# mainboard_V2_1.net
KiCad netlist of a schematic drawn in EasyEDA Pro
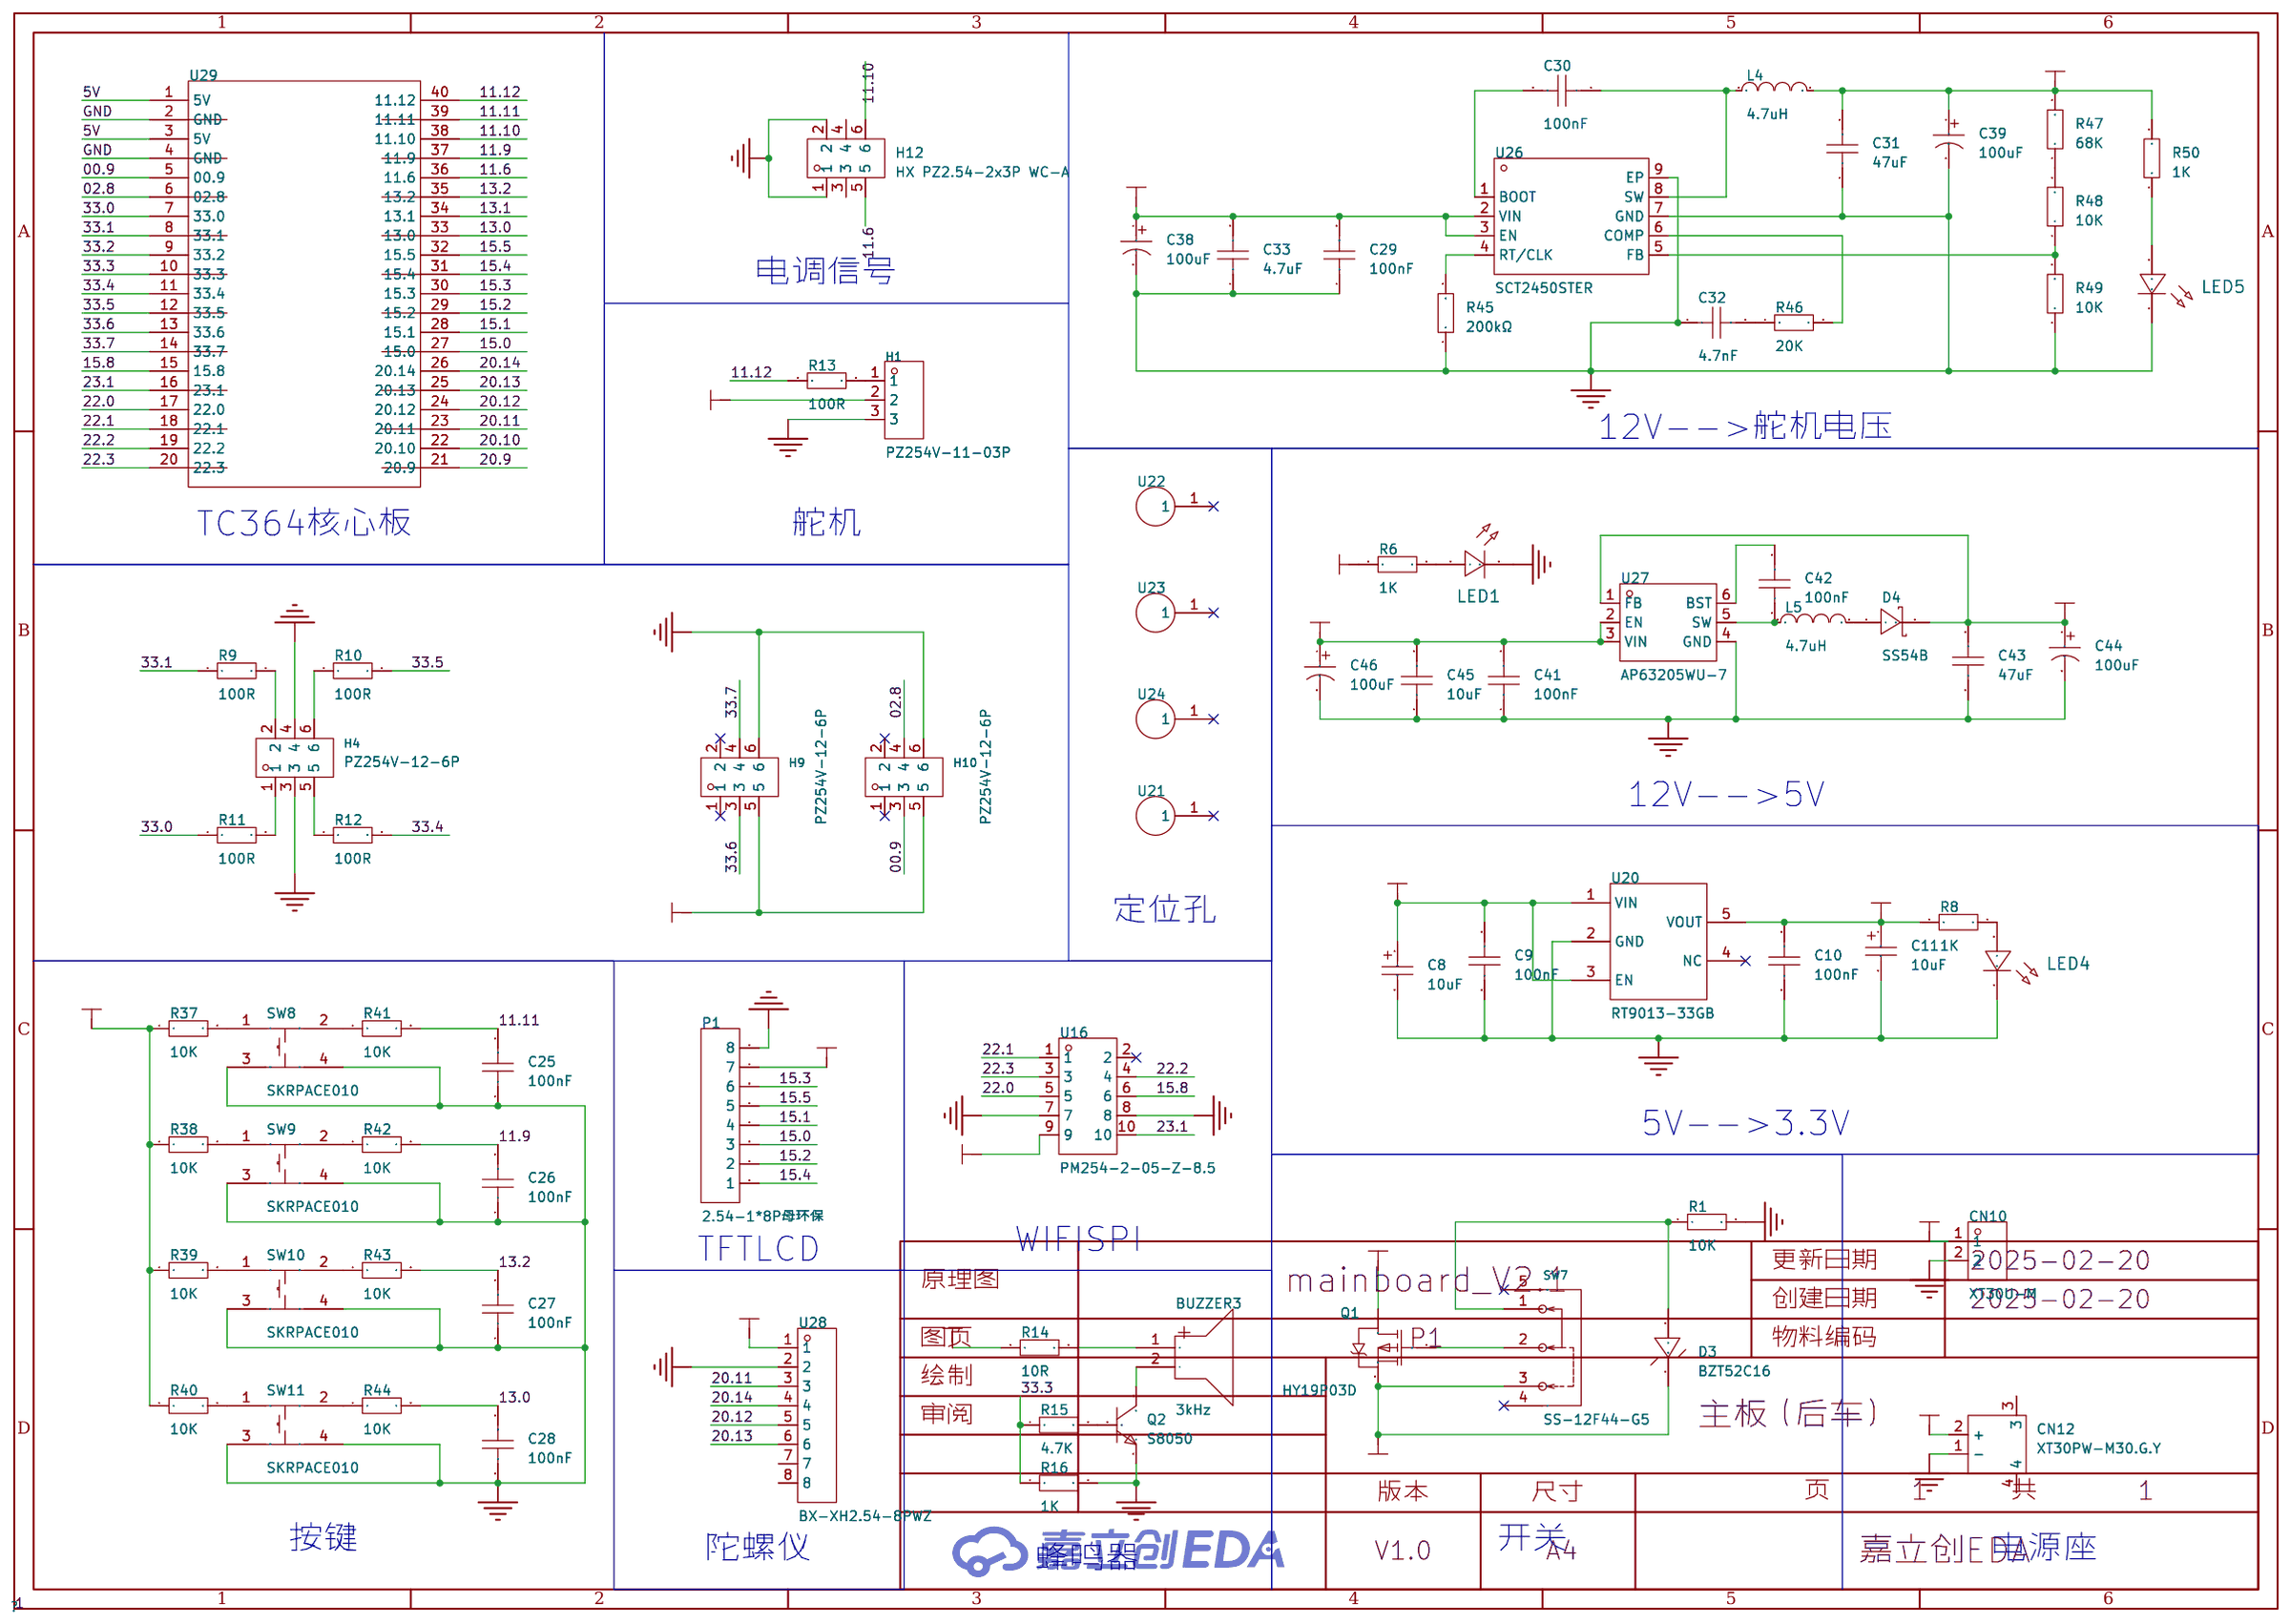
[diagram p0: schematic sheet]

(export (version "E")
  (design (tool "Eeschema 10.0.6"))
  (components
    (comp (ref "BUZZER3")
      (value "3kHz")
      (footprint "easyedapro:BUZ-TH_BD9.0-P5.00-D0.6-FD")
      (description "驱动方式:有源(内含驱动线路);构造类型:电磁式;频率:3kHz;声压(SPL):85dB@10cm;")
      (fields (field (name "Manufacturer Part") "HNB09A03") (field (name "Manufacturer") "华能"))
      (libsource (lib "easyedapro") (part "HNB09A03"))
    )
    (comp (ref "C8")
      (value "10uF")
      (footprint "easyedapro:CAP-SMD_L3.2-W1.6-RD-C7171")
      (description "容值:10uF;精度:±10%;额定电压:16V;等效串联电阻:3Ω@100kHz;")
      (fields (field (name "Manufacturer Part") "TAJA106K016RNJ") (field (name "Manufacturer") "Kyocera AVX"))
      (libsource (lib "easyedapro") (part "TAJA106K016RNJ"))
    )
    (comp (ref "C9")
      (value "100nF")
      (footprint "easyedapro:C0603")
      (description "容值:100nF;精度:±10%;额定电压:50V;材质(温度系数):X7R;")
      (fields
        (field (name "Manufacturer Part") "CC0603KRX7R9BB104")
        (field (name "Manufacturer") "YAGEO(国巨)")
      )
      (libsource (lib "easyedapro") (part "CC0603KRX7R9BB104"))
    )
    (comp (ref "C10")
      (value "100nF")
      (footprint "easyedapro:C0603")
      (description "容值:100nF;精度:±10%;额定电压:50V;材质(温度系数):X7R;")
      (fields
        (field (name "Manufacturer Part") "CC0603KRX7R9BB104")
        (field (name "Manufacturer") "YAGEO(国巨)")
      )
      (libsource (lib "easyedapro") (part "CC0603KRX7R9BB104"))
    )
    (comp (ref "C11")
      (value "10uF")
      (footprint "easyedapro:CAP-SMD_L3.2-W1.6-RD-C7171")
      (description "容值:10uF;精度:±10%;额定电压:16V;等效串联电阻:3Ω@100kHz;")
      (fields (field (name "Manufacturer Part") "TAJA106K016RNJ") (field (name "Manufacturer") "Kyocera AVX"))
      (libsource (lib "easyedapro") (part "TAJA106K016RNJ"))
    )
    (comp (ref "C25")
      (value "100nF")
      (footprint "easyedapro:C0603")
      (libsource (lib "easyedapro") (part "CapAcitance"))
    )
    (comp (ref "C26")
      (value "100nF")
      (footprint "easyedapro:C0603")
      (libsource (lib "easyedapro") (part "CapAcitance"))
    )
    (comp (ref "C27")
      (value "100nF")
      (footprint "easyedapro:C0603")
      (libsource (lib "easyedapro") (part "CapAcitance"))
    )
    (comp (ref "C28")
      (value "100nF")
      (footprint "easyedapro:C0603")
      (libsource (lib "easyedapro") (part "CapAcitance"))
    )
    (comp (ref "C29")
      (value "100nF")
      (footprint "easyedapro:C0603")
      (description "容值:100nF;精度:±10%;额定电压:50V;材质(温度系数):X7R;")
      (fields
        (field (name "Manufacturer Part") "CC0603KRX7R9BB104")
        (field (name "Manufacturer") "YAGEO(国巨)")
      )
      (libsource (lib "easyedapro") (part "CC0603KRX7R9BB104"))
    )
    (comp (ref "C30")
      (value "100nF")
      (footprint "easyedapro:C0603")
      (description "容值:100nF;精度:±10%;额定电压:50V;材质(温度系数):X7R;")
      (fields
        (field (name "Manufacturer Part") "CC0603KRX7R9BB104")
        (field (name "Manufacturer") "YAGEO(国巨)")
      )
      (libsource (lib "easyedapro") (part "CC0603KRX7R9BB104"))
    )
    (comp (ref "C31")
      (value "47uF")
      (footprint "easyedapro:C0805")
      (description "容值:47uF;精度:±20%;额定电压:10V;材质(温度系数):X5R;")
      (fields
        (field (name "Manufacturer Part") "CGA0805X5R476M100MT")
        (field (name "Manufacturer") "HRE(芯声)")
      )
      (libsource (lib "easyedapro") (part "CGA0805X5R476M100MT"))
    )
    (comp (ref "C32")
      (value "4.7nF")
      (footprint "easyedapro:C0603")
      (libsource (lib "easyedapro") (part "CapAcitance"))
    )
    (comp (ref "C33")
      (value "4.7uF")
      (footprint "easyedapro:C0603")
      (libsource (lib "easyedapro") (part "CapAcitance"))
    )
    (comp (ref "C38")
      (value "100uF")
      (footprint "easyedapro:CAP-TH_BD6.3-P2.50-D1.0-FD")
      (description "容值:100uF;精度:±20%;额定电压:35V;纹波电流:2.35A@100kHz;等效串联电阻:50mΩ@100kHz;类型:-;")
      (fields
        (field (name "Manufacturer Part") "SPZ1VM101E08O00RAXXX")
        (field (name "Manufacturer") "AISHI(艾华集团)")
      )
      (libsource (lib "easyedapro") (part "SPZ1VM101E08000R"))
    )
    (comp (ref "C39")
      (value "100uF")
      (footprint "easyedapro:CAP-TH_BD6.3-P2.50-D1.0-FD")
      (description "容值:100uF;精度:±20%;额定电压:35V;纹波电流:2.35A@100kHz;等效串联电阻:50mΩ@100kHz;类型:-;")
      (fields
        (field (name "Manufacturer Part") "SPZ1VM101E08O00RAXXX")
        (field (name "Manufacturer") "AISHI(艾华集团)")
      )
      (libsource (lib "easyedapro") (part "SPZ1VM101E08000R"))
    )
    (comp (ref "C41")
      (value "100nF")
      (footprint "easyedapro:C0603")
      (libsource (lib "easyedapro") (part "CapAcitance"))
    )
    (comp (ref "C42")
      (value "100nF")
      (footprint "easyedapro:C0603")
      (libsource (lib "easyedapro") (part "CapAcitance"))
    )
    (comp (ref "C43")
      (value "47uF")
      (footprint "easyedapro:C0805")
      (description "容值:47uF;精度:±20%;额定电压:10V;材质(温度系数):X5R;")
      (fields
        (field (name "Manufacturer Part") "CGA0805X5R476M100MT")
        (field (name "Manufacturer") "HRE(芯声)")
      )
      (libsource (lib "easyedapro") (part "CGA0805X5R476M100MT"))
    )
    (comp (ref "C44")
      (value "100uF")
      (footprint "easyedapro:CAP-TH_BD6.3-P2.50-D1.0-FD")
      (description "容值:100uF;精度:±20%;额定电压:35V;纹波电流:2.35A@100kHz;等效串联电阻:50mΩ@100kHz;类型:-;")
      (fields
        (field (name "Manufacturer Part") "SPZ1VM101E08O00RAXXX")
        (field (name "Manufacturer") "AISHI(艾华集团)")
      )
      (libsource (lib "easyedapro") (part "SPZ1VM101E08000R"))
    )
    (comp (ref "C45")
      (value "10uF")
      (footprint "easyedapro:C0603")
      (libsource (lib "easyedapro") (part "CapAcitance"))
    )
    (comp (ref "C46")
      (value "100uF")
      (footprint "easyedapro:CAP-TH_BD6.3-P2.50-D1.0-FD")
      (description "容值:100uF;精度:±20%;额定电压:35V;纹波电流:2.35A@100kHz;等效串联电阻:50mΩ@100kHz;类型:-;")
      (fields
        (field (name "Manufacturer Part") "SPZ1VM101E08O00RAXXX")
        (field (name "Manufacturer") "AISHI(艾华集团)")
      )
      (libsource (lib "easyedapro") (part "SPZ1VM101E08000R"))
    )
    (comp (ref "CN10")
      (value "XT30U-M")
      (footprint "easyedapro:CONN-TH_XT30U-M")
      (description "类别:-;类型1:-;")
      (fields (field (name "Manufacturer") "AMASS(艾迈斯)"))
      (libsource (lib "easyedapro") (part "XT30U-M"))
    )
    (comp (ref "CN12")
      (value "XT30PW-M30.G.Y")
      (footprint "easyedapro:CONN-TH_XT30PW-M")
      (description "类别:-;类型1:-;")
      (fields (field (name "Manufacturer") "AMASS(艾迈斯)"))
      (libsource (lib "easyedapro") (part "XT30PW-M"))
    )
    (comp (ref "D3")
      (value "BZT52C16")
      (footprint "easyedapro:SOD-123_L2.7-W1.6-LS3.7-RD")
      (description "二极管配置:独立式;稳压值(标称值):16V;稳压值(范围):15.3V~17.1V;功率:500mW;精度:-;")
      (fields (field (name "Manufacturer") "BORN(伯恩半导体)"))
      (libsource (lib "easyedapro") (part "BZT52C16_C266570"))
    )
    (comp (ref "D4")
      (value "SS54B")
      (footprint "easyedapro:SMB_L4.6-W3.6-LS5.3-RD")
      (description "二极管配置:独立式;正向压降(Vf):550mV@5A;直流反向耐压(Vr):40V;整流电流:5A;")
      (fields (field (name "Manufacturer") "MDD(辰达半导体)"))
      (libsource (lib "easyedapro") (part "SS54"))
    )
    (comp (ref "H1")
      (value "PZ254V-11-03P")
      (footprint "easyedapro:HDR-TH_3P-P2.54-V-M")
      (fields (field (name "Manufacturer") "XFCN(兴飞)"))
      (libsource (lib "easyedapro") (part "PZ254V-11-03P_C2937625"))
    )
    (comp (ref "H4")
      (value "PZ254V-12-6P")
      (footprint "easyedapro:HDR-TH_6P-P2.54-V-M-R2-C3-S2.54")
      (fields (field (name "Manufacturer") "XFCN(兴飞)"))
      (libsource (lib "easyedapro") (part "PZ254V-12-6P"))
    )
    (comp (ref "H9")
      (value "PZ254V-12-6P")
      (footprint "easyedapro:HDR-TH_6P-P2.54-V-M-R2-C3-S2.54")
      (fields (field (name "Manufacturer") "XFCN(兴飞)"))
      (libsource (lib "easyedapro") (part "PZ254V-12-6P"))
    )
    (comp (ref "H10")
      (value "PZ254V-12-6P")
      (footprint "easyedapro:HDR-TH_6P-P2.54-V-M-R2-C3-S2.54")
      (fields (field (name "Manufacturer") "XFCN(兴飞)"))
      (libsource (lib "easyedapro") (part "PZ254V-12-6P"))
    )
    (comp (ref "H12")
      (value "HX PZ2.54-2x3P WC-A")
      (footprint "easyedapro:HDR-TH_6P-P2.54-H-M-R2-C3-S2.54-W12.9")
      (fields (field (name "Manufacturer") "hanxia(韩下)"))
      (libsource (lib "easyedapro") (part "HX PZ2.54-2X3P WC-A"))
    )
    (comp (ref "L4")
      (value "4.7uH")
      (footprint "easyedapro:IND-SMD_L7.0-W6.6")
      (description "电感值:4.7uH;精度:±20%;额定电流:6A;饱和电流(Isat):9A;类型:一体成型电感;")
      (fields (field (name "Manufacturer Part") "FXL0630-4R7-M") (field (name "Manufacturer") "cjiang(长江微电)"))
      (libsource (lib "easyedapro") (part "FXL0630-4R7-M"))
    )
    (comp (ref "L5")
      (value "4.7uH")
      (footprint "easyedapro:IND-SMD_L7.0-W6.6")
      (description "电感值:4.7uH;精度:±20%;额定电流:6A;饱和电流(Isat):9A;类型:一体成型电感;")
      (fields (field (name "Manufacturer Part") "FXL0630-4R7-M") (field (name "Manufacturer") "cjiang(长江微电)"))
      (libsource (lib "easyedapro") (part "FXL0630-4R7-M"))
    )
    (comp (ref "LED1")
      (value "~")
      (footprint "easyedapro:LED_0603")
      (libsource (lib "easyedapro") (part "LED_R"))
    )
    (comp (ref "LED4")
      (value "~")
      (footprint "easyedapro:LED_0603")
      (libsource (lib "easyedapro") (part "LED_R"))
    )
    (comp (ref "LED5")
      (value "~")
      (footprint "easyedapro:LED_0603")
      (libsource (lib "easyedapro") (part "LED_R"))
    )
    (comp (ref "P1")
      (value "2.54-1*8P母环保")
      (footprint "easyedapro:HDR-TH_8P-P2.54-V-F-1")
      (description "插孔结构:1x8P;间距:2.54mm;行距:-;安装类型:直插;排数:单排;总孔位数:8P;塑高:-;触头材质:-;触头镀层:-;")
      (fields (field (name "Manufacturer") "BOOMELE(博穆精密)"))
      (libsource (lib "easyedapro") (part "Header-Female-2.54_1x8"))
    )
    (comp (ref "Q1")
      (value "HY19P03D")
      (footprint "easyedapro:TO-252-2_L6.6-W6.1-P4.57-LS9.9-TL-CW")
      (fields (field (name "Manufacturer") "HUAYI(华羿微)"))
      (libsource (lib "easyedapro") (part "HY19P03D"))
    )
    (comp (ref "Q2")
      (value "S8050")
      (footprint "easyedapro:SOT-23-3_L2.9-W1.3-P1.90-LS2.4-BR")
      (description "晶体管类型:NPN;集电极电流(Ic):500mA;集射极击穿电压(Vceo):25V;功率(Pd):300mW;")
      (fields (field (name "Manufacturer") "YONGYUTAI(永裕泰)"))
      (libsource (lib "easyedapro") (part "S8050_C2891804"))
    )
    (comp (ref "R1") (value "10K") (footprint "easyedapro:R0603") (libsource (lib "easyedapro") (part "电阻")))
    (comp (ref "R6") (value "1K") (footprint "easyedapro:R0603") (libsource (lib "easyedapro") (part "电阻")))
    (comp (ref "R8") (value "1K") (footprint "easyedapro:R0603") (libsource (lib "easyedapro") (part "电阻")))
    (comp (ref "R9") (value "100R") (footprint "easyedapro:R0603") (libsource (lib "easyedapro") (part "电阻")))
    (comp (ref "R10")
      (value "100R")
      (footprint "easyedapro:R0603")
      (libsource (lib "easyedapro") (part "电阻"))
    )
    (comp (ref "R11")
      (value "100R")
      (footprint "easyedapro:R0603")
      (libsource (lib "easyedapro") (part "电阻"))
    )
    (comp (ref "R12")
      (value "100R")
      (footprint "easyedapro:R0603")
      (libsource (lib "easyedapro") (part "电阻"))
    )
    (comp (ref "R13")
      (value "100R")
      (footprint "easyedapro:R0603")
      (libsource (lib "easyedapro") (part "电阻"))
    )
    (comp (ref "R14") (value "10R") (footprint "easyedapro:R0603") (libsource (lib "easyedapro") (part "电阻")))
    (comp (ref "R15")
      (value "4.7K")
      (footprint "easyedapro:R0603")
      (libsource (lib "easyedapro") (part "电阻"))
    )
    (comp (ref "R16") (value "1K") (footprint "easyedapro:R0603") (libsource (lib "easyedapro") (part "电阻")))
    (comp (ref "R37") (value "10K") (footprint "easyedapro:R0603") (libsource (lib "easyedapro") (part "电阻")))
    (comp (ref "R38") (value "10K") (footprint "easyedapro:R0603") (libsource (lib "easyedapro") (part "电阻")))
    (comp (ref "R39") (value "10K") (footprint "easyedapro:R0603") (libsource (lib "easyedapro") (part "电阻")))
    (comp (ref "R40") (value "10K") (footprint "easyedapro:R0603") (libsource (lib "easyedapro") (part "电阻")))
    (comp (ref "R41") (value "10K") (footprint "easyedapro:R0603") (libsource (lib "easyedapro") (part "电阻")))
    (comp (ref "R42") (value "10K") (footprint "easyedapro:R0603") (libsource (lib "easyedapro") (part "电阻")))
    (comp (ref "R43") (value "10K") (footprint "easyedapro:R0603") (libsource (lib "easyedapro") (part "电阻")))
    (comp (ref "R44") (value "10K") (footprint "easyedapro:R0603") (libsource (lib "easyedapro") (part "电阻")))
    (comp (ref "R45")
      (value "200kΩ")
      (footprint "easyedapro:R0603")
      (description "电阻类型:厚膜电阻;阻值:200kΩ;精度:±1%;功率:100mW;最大工作电压:75V;温度系数:±100ppm/°C;")
      (fields
        (field (name "Manufacturer Part") "0603WAF2003T5E")
        (field (name "Manufacturer") "UNI-ROYAL(厚声)")
      )
      (libsource (lib "easyedapro") (part "0603WAF2003T5E"))
    )
    (comp (ref "R46") (value "20K") (footprint "easyedapro:R0603") (libsource (lib "easyedapro") (part "电阻")))
    (comp (ref "R47") (value "68K") (footprint "easyedapro:R0603") (libsource (lib "easyedapro") (part "电阻")))
    (comp (ref "R48") (value "10K") (footprint "easyedapro:R0603") (libsource (lib "easyedapro") (part "电阻")))
    (comp (ref "R49") (value "10K") (footprint "easyedapro:R0603") (libsource (lib "easyedapro") (part "电阻")))
    (comp (ref "R50") (value "1K") (footprint "easyedapro:R0603") (libsource (lib "easyedapro") (part "电阻")))
    (comp (ref "SW7")
      (value "SS-12F44-G5")
      (footprint "easyedapro:SW-TH_SS-12F44-G5")
      (description "额定电流(DC):-;额定电压(DC):-;额定电流(AC):-;额定电压(AC):-;电路结构:单刀双掷;安装方式:直插;机械寿命:5千次;")
      (fields (field (name "Manufacturer") "韩国韩荣"))
      (libsource (lib "easyedapro") (part "SS-12F44-G5"))
    )
    (comp (ref "SW8")
      (value "SKRPACE010")
      (footprint "easyedapro:KEY-SMD_4P-L4.2-W3.2-P2.20-LS4.6")
      (description "电路结构:单刀单掷;按钮形状:椭圆形按钮;安装方式:立贴;开关长度:4.2mm;开关宽度:3.2mm;开关高度:2.5mm;触点电流:50mA;额定电压(DC):16V;带灯:-;机械寿命:-;")
      (fields (field (name "Manufacturer") "ALPSALPINE(阿尔卑斯阿尔派)"))
      (libsource (lib "easyedapro") (part "SKRPACE010"))
    )
    (comp (ref "SW9")
      (value "SKRPACE010")
      (footprint "easyedapro:KEY-SMD_4P-L4.2-W3.2-P2.20-LS4.6")
      (description "电路结构:单刀单掷;按钮形状:椭圆形按钮;安装方式:立贴;开关长度:4.2mm;开关宽度:3.2mm;开关高度:2.5mm;触点电流:50mA;额定电压(DC):16V;带灯:-;机械寿命:-;")
      (fields (field (name "Manufacturer") "ALPSALPINE(阿尔卑斯阿尔派)"))
      (libsource (lib "easyedapro") (part "SKRPACE010"))
    )
    (comp (ref "SW10")
      (value "SKRPACE010")
      (footprint "easyedapro:KEY-SMD_4P-L4.2-W3.2-P2.20-LS4.6")
      (description "电路结构:单刀单掷;按钮形状:椭圆形按钮;安装方式:立贴;开关长度:4.2mm;开关宽度:3.2mm;开关高度:2.5mm;触点电流:50mA;额定电压(DC):16V;带灯:-;机械寿命:-;")
      (fields (field (name "Manufacturer") "ALPSALPINE(阿尔卑斯阿尔派)"))
      (libsource (lib "easyedapro") (part "SKRPACE010"))
    )
    (comp (ref "SW11")
      (value "SKRPACE010")
      (footprint "easyedapro:KEY-SMD_4P-L4.2-W3.2-P2.20-LS4.6")
      (description "电路结构:单刀单掷;按钮形状:椭圆形按钮;安装方式:立贴;开关长度:4.2mm;开关宽度:3.2mm;开关高度:2.5mm;触点电流:50mA;额定电压(DC):16V;带灯:-;机械寿命:-;")
      (fields (field (name "Manufacturer") "ALPSALPINE(阿尔卑斯阿尔派)"))
      (libsource (lib "easyedapro") (part "SKRPACE010"))
    )
    (comp (ref "U16")
      (value "PM254-2-05-Z-8.5")
      (footprint "easyedapro:HDR-TH_10P-P2.54-V-F-R2-C5-S2.54")
      (fields (field (name "Manufacturer") "HCTL(华灿天禄)"))
      (libsource (lib "easyedapro") (part "PM254-2-05-Z-8.5"))
    )
    (comp (ref "U20")
      (value "RT9013-33GB")
      (footprint "easyedapro:SOT-23-5_L3.0-W1.7-P0.95-LS2.8-BL")
      (description "输出类型:固定;输出极性:正;最大输入电压:5.5V;输出电压:3.3V;输出电流:500mA;电源纹波抑制比(PSRR):50dB@(10kHz);")
      (fields (field (name "Manufacturer") "RICHTEK(立锜)"))
      (libsource (lib "easyedapro") (part "RT9013-33GB"))
    )
    (comp (ref "U21")
      (value "~")
      (footprint "easyedapro:M3螺丝孔")
      (libsource (lib "easyedapro") (part "M3螺丝孔"))
    )
    (comp (ref "U22")
      (value "~")
      (footprint "easyedapro:M3螺丝孔")
      (libsource (lib "easyedapro") (part "M3螺丝孔"))
    )
    (comp (ref "U23")
      (value "~")
      (footprint "easyedapro:M3螺丝孔")
      (libsource (lib "easyedapro") (part "M3螺丝孔"))
    )
    (comp (ref "U24")
      (value "~")
      (footprint "easyedapro:M3螺丝孔")
      (libsource (lib "easyedapro") (part "M3螺丝孔"))
    )
    (comp (ref "U26")
      (value "SCT2450STER")
      (footprint "easyedapro:ESOP-8_L4.9-W3.9-P1.27-LS6.0-BL-EP")
      (fields (field (name "Manufacturer") "SCT(芯洲科技)"))
      (libsource (lib "easyedapro") (part "SCT2450STER"))
    )
    (comp (ref "U27")
      (value "AP63205WU-7")
      (footprint "easyedapro:TSOT-23-6_L2.9-W1.6-P0.95-LS2.8-BL")
      (description "功能类型:降压型;输出类型:固定;输入电压:3.8V~32V;输出电压:5V;输出电流:2A;")
      (fields (field (name "Manufacturer") "DIODES(美台)"))
      (libsource (lib "easyedapro") (part "AP63205WU-7"))
    )
    (comp (ref "U28")
      (value "BX-XH2.54-8PWZ")
      (footprint "easyedapro:CONN-TH_8P-P2.50_BX-XH2.54-8PWZ")
      (fields (field (name "Manufacturer") "Bossie(博锡)"))
      (libsource (lib "easyedapro") (part "BX-XH2.54-8PWZ"))
    )
    (comp (ref "U29")
      (value "~")
      (footprint "easyedapro:TC364_CoreBoard_V3.0")
      (libsource (lib "easyedapro") (part "TC364_CoreBoard_V3.0"))
    )
  )
  (nets
    (net (code "1") (name "/00.9") (class "Default")
      (node (ref "H10") (pin "3") (pinfunction "3_3") (pintype "input"))
      (node (ref "U29") (pin "5") (pinfunction "00.9_5") (pintype "input"))
    )
    (net (code "2") (name "/02.8") (class "Default")
      (node (ref "H10") (pin "4") (pinfunction "4_4") (pintype "input"))
      (node (ref "U29") (pin "6") (pinfunction "02.8_6") (pintype "input"))
    )
    (net (code "3") (name "/11.6") (class "Default")
      (node (ref "H12") (pin "5") (pinfunction "5_5") (pintype "unspecified"))
      (node (ref "U29") (pin "36") (pinfunction "11.6_36") (pintype "input"))
    )
    (net (code "4") (name "/11.9") (class "Default")
      (node (ref "C26") (pin "2") (pinfunction "2_2") (pintype "input"))
      (node (ref "R42") (pin "2") (pinfunction "2_2") (pintype "input"))
      (node (ref "U29") (pin "37") (pinfunction "11.9_37") (pintype "input"))
    )
    (net (code "5") (name "/11.10") (class "Default")
      (node (ref "H12") (pin "6") (pinfunction "6_6") (pintype "unspecified"))
      (node (ref "U29") (pin "38") (pinfunction "11.10_38") (pintype "input"))
    )
    (net (code "6") (name "/11.11") (class "Default")
      (node (ref "C25") (pin "2") (pinfunction "2_2") (pintype "input"))
      (node (ref "R41") (pin "2") (pinfunction "2_2") (pintype "input"))
      (node (ref "U29") (pin "39") (pinfunction "11.11_39") (pintype "input"))
    )
    (net (code "7") (name "/11.12") (class "Default")
      (node (ref "R13") (pin "1") (pinfunction "1_1") (pintype "input"))
      (node (ref "U29") (pin "40") (pinfunction "11.12_40") (pintype "input"))
    )
    (net (code "8") (name "/13.0") (class "Default")
      (node (ref "C28") (pin "2") (pinfunction "2_2") (pintype "input"))
      (node (ref "R44") (pin "2") (pinfunction "2_2") (pintype "input"))
      (node (ref "U29") (pin "33") (pinfunction "13.0_33") (pintype "input"))
    )
    (net (code "9") (name "/13.1") (class "Default")
      (node (ref "U29") (pin "34") (pinfunction "13.1_34") (pintype "input"))
    )
    (net (code "10") (name "/13.2") (class "Default")
      (node (ref "C27") (pin "2") (pinfunction "2_2") (pintype "input"))
      (node (ref "R43") (pin "2") (pinfunction "2_2") (pintype "input"))
      (node (ref "U29") (pin "35") (pinfunction "13.2_35") (pintype "input"))
    )
    (net (code "11") (name "/15.0") (class "Default")
      (node (ref "P1") (pin "3") (pinfunction "3_3") (pintype "input"))
      (node (ref "U29") (pin "27") (pinfunction "15.0_27") (pintype "input"))
    )
    (net (code "12") (name "/15.1") (class "Default")
      (node (ref "P1") (pin "4") (pinfunction "4_4") (pintype "input"))
      (node (ref "U29") (pin "28") (pinfunction "15.1_28") (pintype "input"))
    )
    (net (code "13") (name "/15.2") (class "Default")
      (node (ref "P1") (pin "2") (pinfunction "2_2") (pintype "input"))
      (node (ref "U29") (pin "29") (pinfunction "15.2_29") (pintype "input"))
    )
    (net (code "14") (name "/15.3") (class "Default")
      (node (ref "P1") (pin "6") (pinfunction "6_6") (pintype "input"))
      (node (ref "U29") (pin "30") (pinfunction "15.3_30") (pintype "input"))
    )
    (net (code "15") (name "/15.4") (class "Default")
      (node (ref "P1") (pin "1") (pinfunction "1_1") (pintype "input"))
      (node (ref "U29") (pin "31") (pinfunction "15.4_31") (pintype "input"))
    )
    (net (code "16") (name "/15.5") (class "Default")
      (node (ref "P1") (pin "5") (pinfunction "5_5") (pintype "input"))
      (node (ref "U29") (pin "32") (pinfunction "15.5_32") (pintype "input"))
    )
    (net (code "17") (name "/15.8") (class "Default")
      (node (ref "U16") (pin "6") (pinfunction "6_6") (pintype "unspecified"))
      (node (ref "U29") (pin "15") (pinfunction "15.8_15") (pintype "input"))
    )
    (net (code "18") (name "/20.9") (class "Default")
      (node (ref "U29") (pin "21") (pinfunction "20.9_21") (pintype "input"))
    )
    (net (code "19") (name "/20.10") (class "Default")
      (node (ref "U29") (pin "22") (pinfunction "20.10_22") (pintype "input"))
    )
    (net (code "20") (name "/20.11") (class "Default")
      (node (ref "U28") (pin "3") (pinfunction "3_3") (pintype "unspecified"))
      (node (ref "U29") (pin "23") (pinfunction "20.11_23") (pintype "input"))
    )
    (net (code "21") (name "/20.12") (class "Default")
      (node (ref "U28") (pin "5") (pinfunction "5_5") (pintype "unspecified"))
      (node (ref "U29") (pin "24") (pinfunction "20.12_24") (pintype "input"))
    )
    (net (code "22") (name "/20.13") (class "Default")
      (node (ref "U28") (pin "6") (pinfunction "6_6") (pintype "unspecified"))
      (node (ref "U29") (pin "25") (pinfunction "20.13_25") (pintype "input"))
    )
    (net (code "23") (name "/20.14") (class "Default")
      (node (ref "U28") (pin "4") (pinfunction "4_4") (pintype "unspecified"))
      (node (ref "U29") (pin "26") (pinfunction "20.14_26") (pintype "input"))
    )
    (net (code "24") (name "/22.0") (class "Default")
      (node (ref "U16") (pin "5") (pinfunction "5_5") (pintype "unspecified"))
      (node (ref "U29") (pin "17") (pinfunction "22.0_17") (pintype "input"))
    )
    (net (code "25") (name "/22.1") (class "Default")
      (node (ref "U16") (pin "1") (pinfunction "1_1") (pintype "unspecified"))
      (node (ref "U29") (pin "18") (pinfunction "22.1_18") (pintype "input"))
    )
    (net (code "26") (name "/22.2") (class "Default")
      (node (ref "U16") (pin "4") (pinfunction "4_4") (pintype "unspecified"))
      (node (ref "U29") (pin "19") (pinfunction "22.2_19") (pintype "input"))
    )
    (net (code "27") (name "/22.3") (class "Default")
      (node (ref "U16") (pin "3") (pinfunction "3_3") (pintype "unspecified"))
      (node (ref "U29") (pin "20") (pinfunction "22.3_20") (pintype "input"))
    )
    (net (code "28") (name "/23.1") (class "Default")
      (node (ref "U16") (pin "10") (pinfunction "10_10") (pintype "unspecified"))
      (node (ref "U29") (pin "16") (pinfunction "23.1_16") (pintype "input"))
    )
    (net (code "29") (name "/33.0") (class "Default")
      (node (ref "R11") (pin "1") (pinfunction "1_1") (pintype "input"))
      (node (ref "U29") (pin "7") (pinfunction "33.0_7") (pintype "input"))
    )
    (net (code "30") (name "/33.1") (class "Default")
      (node (ref "R9") (pin "1") (pinfunction "1_1") (pintype "input"))
      (node (ref "U29") (pin "8") (pinfunction "33.1_8") (pintype "input"))
    )
    (net (code "31") (name "/33.2") (class "Default")
      (node (ref "U29") (pin "9") (pinfunction "33.2_9") (pintype "input"))
    )
    (net (code "32") (name "/33.3") (class "Default")
      (node (ref "R15") (pin "1") (pinfunction "1_1") (pintype "input"))
      (node (ref "R16") (pin "1") (pinfunction "1_1") (pintype "input"))
      (node (ref "U29") (pin "10") (pinfunction "33.3_10") (pintype "input"))
    )
    (net (code "33") (name "/33.4") (class "Default")
      (node (ref "R12") (pin "2") (pinfunction "2_2") (pintype "input"))
      (node (ref "U29") (pin "11") (pinfunction "33.4_11") (pintype "input"))
    )
    (net (code "34") (name "/33.5") (class "Default")
      (node (ref "R10") (pin "2") (pinfunction "2_2") (pintype "input"))
      (node (ref "U29") (pin "12") (pinfunction "33.5_12") (pintype "input"))
    )
    (net (code "35") (name "/33.6") (class "Default")
      (node (ref "H9") (pin "3") (pinfunction "3_3") (pintype "input"))
      (node (ref "U29") (pin "13") (pinfunction "33.6_13") (pintype "input"))
    )
    (net (code "36") (name "/33.7") (class "Default")
      (node (ref "H9") (pin "4") (pinfunction "4_4") (pintype "input"))
      (node (ref "U29") (pin "14") (pinfunction "33.7_14") (pintype "input"))
    )
    (net (code "37") (name "3V3") (class "Default")
      (node (ref "C10") (pin "2") (pinfunction "2_2") (pintype "unspecified"))
      (node (ref "C11") (pin "1") (pinfunction "1_1") (pintype "input"))
      (node (ref "H10") (pin "5") (pinfunction "5_5") (pintype "input"))
      (node (ref "H9") (pin "5") (pinfunction "5_5") (pintype "input"))
      (node (ref "P1") (pin "7") (pinfunction "7_7") (pintype "input"))
      (node (ref "R14") (pin "1") (pinfunction "1_1") (pintype "input"))
      (node (ref "R37") (pin "1") (pinfunction "1_1") (pintype "input"))
      (node (ref "R38") (pin "1") (pinfunction "1_1") (pintype "input"))
      (node (ref "R39") (pin "1") (pinfunction "1_1") (pintype "input"))
      (node (ref "R40") (pin "1") (pinfunction "1_1") (pintype "input"))
      (node (ref "R8") (pin "2") (pinfunction "2_2") (pintype "input"))
      (node (ref "U20") (pin "5") (pinfunction "VOUT_5") (pintype "unspecified"))
      (node (ref "U28") (pin "1") (pinfunction "1_1") (pintype "unspecified"))
    )
    (net (code "38") (name "5V") (class "Default")
      (node (ref "C43") (pin "2") (pinfunction "2_2") (pintype "unspecified"))
      (node (ref "C44") (pin "1") (pinfunction "1_1") (pintype "input"))
      (node (ref "C8") (pin "1") (pinfunction "1_1") (pintype "input"))
      (node (ref "C9") (pin "2") (pinfunction "2_2") (pintype "unspecified"))
      (node (ref "D4") (pin "1") (pinfunction "K_1") (pintype "unspecified"))
      (node (ref "R6") (pin "2") (pinfunction "2_2") (pintype "input"))
      (node (ref "U16") (pin "9") (pinfunction "9_9") (pintype "unspecified"))
      (node (ref "U20") (pin "1") (pinfunction "VIN_1") (pintype "unspecified"))
      (node (ref "U20") (pin "3") (pinfunction "EN_3") (pintype "unspecified"))
      (node (ref "U27") (pin "1") (pinfunction "FB_1") (pintype "unspecified"))
      (node (ref "U29") (pin "1") (pinfunction "5V_1") (pintype "input"))
      (node (ref "U29") (pin "3") (pinfunction "5V_3") (pintype "input"))
    )
    (net (code "39") (name "GND") (class "Default")
      (node (ref "C10") (pin "1") (pinfunction "1_1") (pintype "unspecified"))
      (node (ref "C11") (pin "2") (pinfunction "2_2") (pintype "input"))
      (node (ref "C25") (pin "1") (pinfunction "1_1") (pintype "input"))
      (node (ref "C26") (pin "1") (pinfunction "1_1") (pintype "input"))
      (node (ref "C27") (pin "1") (pinfunction "1_1") (pintype "input"))
      (node (ref "C28") (pin "1") (pinfunction "1_1") (pintype "input"))
      (node (ref "C29") (pin "1") (pinfunction "1_1") (pintype "unspecified"))
      (node (ref "C31") (pin "1") (pinfunction "1_1") (pintype "unspecified"))
      (node (ref "C32") (pin "1") (pinfunction "1_1") (pintype "input"))
      (node (ref "C33") (pin "1") (pinfunction "1_1") (pintype "input"))
      (node (ref "C38") (pin "2") (pinfunction "2_2") (pintype "input"))
      (node (ref "C39") (pin "2") (pinfunction "2_2") (pintype "input"))
      (node (ref "C41") (pin "1") (pinfunction "1_1") (pintype "input"))
      (node (ref "C43") (pin "1") (pinfunction "1_1") (pintype "unspecified"))
      (node (ref "C44") (pin "2") (pinfunction "2_2") (pintype "input"))
      (node (ref "C45") (pin "1") (pinfunction "1_1") (pintype "input"))
      (node (ref "C46") (pin "2") (pinfunction "2_2") (pintype "input"))
      (node (ref "C8") (pin "2") (pinfunction "2_2") (pintype "input"))
      (node (ref "C9") (pin "1") (pinfunction "1_1") (pintype "unspecified"))
      (node (ref "CN10") (pin "2") (pinfunction "2_2") (pintype "unspecified"))
      (node (ref "CN12") (pin "1") (pinfunction "-_1") (pintype "unspecified"))
      (node (ref "H1") (pin "3") (pinfunction "3_3") (pintype "unspecified"))
      (node (ref "H10") (pin "6") (pinfunction "6_6") (pintype "input"))
      (node (ref "H12") (pin "1") (pinfunction "1_1") (pintype "unspecified"))
      (node (ref "H12") (pin "2") (pinfunction "2_2") (pintype "unspecified"))
      (node (ref "H4") (pin "3") (pinfunction "3_3") (pintype "input"))
      (node (ref "H4") (pin "4") (pinfunction "4_4") (pintype "input"))
      (node (ref "H9") (pin "6") (pinfunction "6_6") (pintype "input"))
      (node (ref "LED1") (pin "1") (pinfunction "C_1") (pintype "input"))
      (node (ref "LED4") (pin "1") (pinfunction "C_1") (pintype "input"))
      (node (ref "LED5") (pin "1") (pinfunction "C_1") (pintype "input"))
      (node (ref "P1") (pin "8") (pinfunction "8_8") (pintype "input"))
      (node (ref "Q2") (pin "2") (pinfunction "E_2") (pintype "unspecified"))
      (node (ref "R1") (pin "2") (pinfunction "2_2") (pintype "input"))
      (node (ref "R16") (pin "2") (pinfunction "2_2") (pintype "input"))
      (node (ref "R45") (pin "1") (pinfunction "1_1") (pintype "input"))
      (node (ref "R49") (pin "1") (pinfunction "1_1") (pintype "input"))
      (node (ref "SW10") (pin "3") (pinfunction "3_3") (pintype "unspecified"))
      (node (ref "SW10") (pin "4") (pinfunction "4_4") (pintype "unspecified"))
      (node (ref "SW11") (pin "3") (pinfunction "3_3") (pintype "unspecified"))
      (node (ref "SW11") (pin "4") (pinfunction "4_4") (pintype "unspecified"))
      (node (ref "SW8") (pin "3") (pinfunction "3_3") (pintype "unspecified"))
      (node (ref "SW8") (pin "4") (pinfunction "4_4") (pintype "unspecified"))
      (node (ref "SW9") (pin "3") (pinfunction "3_3") (pintype "unspecified"))
      (node (ref "SW9") (pin "4") (pinfunction "4_4") (pintype "unspecified"))
      (node (ref "U16") (pin "7") (pinfunction "7_7") (pintype "unspecified"))
      (node (ref "U16") (pin "8") (pinfunction "8_8") (pintype "unspecified"))
      (node (ref "U20") (pin "2") (pinfunction "GND_2") (pintype "unspecified"))
      (node (ref "U26") (pin "7") (pinfunction "GND_7") (pintype "input"))
      (node (ref "U26") (pin "9") (pinfunction "EP_9") (pintype "input"))
      (node (ref "U27") (pin "4") (pinfunction "GND_4") (pintype "unspecified"))
      (node (ref "U28") (pin "2") (pinfunction "2_2") (pintype "unspecified"))
      (node (ref "U29") (pin "2") (pinfunction "GND_2") (pintype "input"))
      (node (ref "U29") (pin "4") (pinfunction "GND_4") (pintype "input"))
    )
    (net (code "40") (name "Net-(BUZZER3-+)") (class "Default")
      (node (ref "BUZZER3") (pin "1") (pinfunction "+_1") (pintype "unspecified"))
      (node (ref "R14") (pin "2") (pinfunction "2_2") (pintype "input"))
    )
    (net (code "41") (name "Net-(BUZZER3--)") (class "Default")
      (node (ref "BUZZER3") (pin "2") (pinfunction "-_2") (pintype "unspecified"))
      (node (ref "Q2") (pin "3") (pinfunction "C_3") (pintype "unspecified"))
    )
    (net (code "42") (name "Net-(C32-Pad2)") (class "Default")
      (node (ref "C32") (pin "2") (pinfunction "2_2") (pintype "input"))
      (node (ref "R46") (pin "1") (pinfunction "1_1") (pintype "input"))
    )
    (net (code "43") (name "Net-(D3-Pad2)") (class "Default")
      (node (ref "D3") (pin "2") (pinfunction "2_2") (pintype "unspecified"))
      (node (ref "R1") (pin "1") (pinfunction "1_1") (pintype "input"))
      (node (ref "SW7") (pin "1") (pinfunction "1_1") (pintype "input"))
    )
    (net (code "44") (name "Net-(D4-A)") (class "Default")
      (node (ref "D4") (pin "2") (pinfunction "A_2") (pintype "unspecified"))
      (node (ref "L5") (pin "2") (pinfunction "2_2") (pintype "unspecified"))
    )
    (net (code "45") (name "Net-(H1-Pad1)") (class "Default")
      (node (ref "H1") (pin "1") (pinfunction "1_1") (pintype "unspecified"))
      (node (ref "R13") (pin "2") (pinfunction "2_2") (pintype "input"))
    )
    (net (code "46") (name "Net-(H4-Pad1)") (class "Default")
      (node (ref "H4") (pin "1") (pinfunction "1_1") (pintype "input"))
      (node (ref "R11") (pin "2") (pinfunction "2_2") (pintype "input"))
    )
    (net (code "47") (name "Net-(H4-Pad2)") (class "Default")
      (node (ref "H4") (pin "2") (pinfunction "2_2") (pintype "input"))
      (node (ref "R9") (pin "2") (pinfunction "2_2") (pintype "input"))
    )
    (net (code "48") (name "Net-(H4-Pad5)") (class "Default")
      (node (ref "H4") (pin "5") (pinfunction "5_5") (pintype "input"))
      (node (ref "R12") (pin "1") (pinfunction "1_1") (pintype "input"))
    )
    (net (code "49") (name "Net-(H4-Pad6)") (class "Default")
      (node (ref "H4") (pin "6") (pinfunction "6_6") (pintype "input"))
      (node (ref "R10") (pin "1") (pinfunction "1_1") (pintype "input"))
    )
    (net (code "50") (name "Net-(LED1-A)") (class "Default")
      (node (ref "LED1") (pin "2") (pinfunction "A_2") (pintype "input"))
      (node (ref "R6") (pin "1") (pinfunction "1_1") (pintype "input"))
    )
    (net (code "51") (name "Net-(LED4-A)") (class "Default")
      (node (ref "LED4") (pin "2") (pinfunction "A_2") (pintype "input"))
      (node (ref "R8") (pin "1") (pinfunction "1_1") (pintype "input"))
    )
    (net (code "52") (name "Net-(LED5-A)") (class "Default")
      (node (ref "LED5") (pin "2") (pinfunction "A_2") (pintype "input"))
      (node (ref "R50") (pin "1") (pinfunction "1_1") (pintype "input"))
    )
    (net (code "53") (name "Net-(Q1-G)") (class "Default")
      (node (ref "Q1") (pin "1") (pinfunction "G_1") (pintype "input"))
      (node (ref "SW7") (pin "2") (pinfunction "2_2") (pintype "input"))
    )
    (net (code "54") (name "Net-(Q2-B)") (class "Default")
      (node (ref "Q2") (pin "1") (pinfunction "B_1") (pintype "unspecified"))
      (node (ref "R15") (pin "2") (pinfunction "2_2") (pintype "input"))
    )
    (net (code "55") (name "Net-(R37-Pad2)") (class "Default")
      (node (ref "R37") (pin "2") (pinfunction "2_2") (pintype "input"))
      (node (ref "SW8") (pin "1") (pinfunction "1_1") (pintype "unspecified"))
    )
    (net (code "56") (name "Net-(R38-Pad2)") (class "Default")
      (node (ref "R38") (pin "2") (pinfunction "2_2") (pintype "input"))
      (node (ref "SW9") (pin "1") (pinfunction "1_1") (pintype "unspecified"))
    )
    (net (code "57") (name "Net-(R39-Pad2)") (class "Default")
      (node (ref "R39") (pin "2") (pinfunction "2_2") (pintype "input"))
      (node (ref "SW10") (pin "1") (pinfunction "1_1") (pintype "unspecified"))
    )
    (net (code "58") (name "Net-(R40-Pad2)") (class "Default")
      (node (ref "R40") (pin "2") (pinfunction "2_2") (pintype "input"))
      (node (ref "SW11") (pin "1") (pinfunction "1_1") (pintype "unspecified"))
    )
    (net (code "59") (name "Net-(R41-Pad1)") (class "Default")
      (node (ref "R41") (pin "1") (pinfunction "1_1") (pintype "input"))
      (node (ref "SW8") (pin "2") (pinfunction "2_2") (pintype "unspecified"))
    )
    (net (code "60") (name "Net-(R42-Pad1)") (class "Default")
      (node (ref "R42") (pin "1") (pinfunction "1_1") (pintype "input"))
      (node (ref "SW9") (pin "2") (pinfunction "2_2") (pintype "unspecified"))
    )
    (net (code "61") (name "Net-(R43-Pad1)") (class "Default")
      (node (ref "R43") (pin "1") (pinfunction "1_1") (pintype "input"))
      (node (ref "SW10") (pin "2") (pinfunction "2_2") (pintype "unspecified"))
    )
    (net (code "62") (name "Net-(R44-Pad1)") (class "Default")
      (node (ref "R44") (pin "1") (pinfunction "1_1") (pintype "input"))
      (node (ref "SW11") (pin "2") (pinfunction "2_2") (pintype "unspecified"))
    )
    (net (code "63") (name "Net-(R47-Pad1)") (class "Default")
      (node (ref "R47") (pin "1") (pinfunction "1_1") (pintype "input"))
      (node (ref "R48") (pin "2") (pinfunction "2_2") (pintype "input"))
    )
    (net (code "64") (name "Net-(U26-BOOT)") (class "Default")
      (node (ref "C30") (pin "2") (pinfunction "2_2") (pintype "unspecified"))
      (node (ref "U26") (pin "1") (pinfunction "BOOT_1") (pintype "input"))
    )
    (net (code "65") (name "Net-(U26-COMP)") (class "Default")
      (node (ref "R46") (pin "2") (pinfunction "2_2") (pintype "input"))
      (node (ref "U26") (pin "6") (pinfunction "COMP_6") (pintype "input"))
    )
    (net (code "66") (name "Net-(U26-FB)") (class "Default")
      (node (ref "R48") (pin "1") (pinfunction "1_1") (pintype "input"))
      (node (ref "R49") (pin "2") (pinfunction "2_2") (pintype "input"))
      (node (ref "U26") (pin "5") (pinfunction "FB_5") (pintype "input"))
    )
    (net (code "67") (name "Net-(U26-RT{slash}CLK)") (class "Default")
      (node (ref "R45") (pin "2") (pinfunction "2_2") (pintype "input"))
      (node (ref "U26") (pin "4") (pinfunction "RT/CLK_4") (pintype "input"))
    )
    (net (code "68") (name "Net-(U26-SW)") (class "Default")
      (node (ref "C30") (pin "1") (pinfunction "1_1") (pintype "unspecified"))
      (node (ref "L4") (pin "1") (pinfunction "1_1") (pintype "unspecified"))
      (node (ref "U26") (pin "8") (pinfunction "SW_8") (pintype "input"))
    )
    (net (code "69") (name "Net-(U27-BST)") (class "Default")
      (node (ref "C42") (pin "2") (pinfunction "2_2") (pintype "input"))
      (node (ref "U27") (pin "6") (pinfunction "BST_6") (pintype "unspecified"))
    )
    (net (code "70") (name "Net-(U27-SW)") (class "Default")
      (node (ref "C42") (pin "1") (pinfunction "1_1") (pintype "input"))
      (node (ref "L5") (pin "1") (pinfunction "1_1") (pintype "unspecified"))
      (node (ref "U27") (pin "5") (pinfunction "SW_5") (pintype "unspecified"))
    )
    (net (code "71") (name "VCCBAT") (class "Default")
      (node (ref "C29") (pin "2") (pinfunction "2_2") (pintype "unspecified"))
      (node (ref "C33") (pin "2") (pinfunction "2_2") (pintype "input"))
      (node (ref "C38") (pin "1") (pinfunction "1_1") (pintype "input"))
      (node (ref "C41") (pin "2") (pinfunction "2_2") (pintype "input"))
      (node (ref "C45") (pin "2") (pinfunction "2_2") (pintype "input"))
      (node (ref "C46") (pin "1") (pinfunction "1_1") (pintype "input"))
      (node (ref "CN12") (pin "2") (pinfunction "+_2") (pintype "unspecified"))
      (node (ref "Q1") (pin "2") (pinfunction "D_2") (pintype "input"))
      (node (ref "U26") (pin "2") (pinfunction "VIN_2") (pintype "input"))
      (node (ref "U26") (pin "3") (pinfunction "EN_3") (pintype "input"))
      (node (ref "U27") (pin "2") (pinfunction "EN_2") (pintype "unspecified"))
      (node (ref "U27") (pin "3") (pinfunction "VIN_3") (pintype "unspecified"))
    )
    (net (code "72") (name "VCCSTEER") (class "Default")
      (node (ref "C31") (pin "2") (pinfunction "2_2") (pintype "unspecified"))
      (node (ref "C39") (pin "1") (pinfunction "1_1") (pintype "input"))
      (node (ref "H1") (pin "2") (pinfunction "2_2") (pintype "unspecified"))
      (node (ref "L4") (pin "2") (pinfunction "2_2") (pintype "unspecified"))
      (node (ref "R47") (pin "2") (pinfunction "2_2") (pintype "input"))
      (node (ref "R50") (pin "2") (pinfunction "2_2") (pintype "input"))
    )
    (net (code "73") (name "VIN") (class "Default")
      (node (ref "CN10") (pin "1") (pinfunction "1_1") (pintype "unspecified"))
      (node (ref "D3") (pin "1") (pinfunction "1_1") (pintype "unspecified"))
      (node (ref "Q1") (pin "3") (pinfunction "S_3") (pintype "input"))
      (node (ref "SW7") (pin "3") (pinfunction "3_3") (pintype "input"))
    )
    (net (code "74") (name "unconnected-(CN12-Pad3)") (class "Default")
      (node (ref "CN12") (pin "3") (pinfunction "3_3") (pintype "unspecified"))
    )
    (net (code "75") (name "unconnected-(CN12-Pad4)") (class "Default")
      (node (ref "CN12") (pin "4") (pinfunction "4_4") (pintype "unspecified"))
    )
    (net (code "76") (name "unconnected-(H9-Pad1)") (class "Default")
      (node (ref "H9") (pin "1") (pinfunction "1_1") (pintype "input+no_connect"))
    )
    (net (code "77") (name "unconnected-(H9-Pad2)") (class "Default")
      (node (ref "H9") (pin "2") (pinfunction "2_2") (pintype "input+no_connect"))
    )
    (net (code "78") (name "unconnected-(H10-Pad1)") (class "Default")
      (node (ref "H10") (pin "1") (pinfunction "1_1") (pintype "input+no_connect"))
    )
    (net (code "79") (name "unconnected-(H10-Pad2)") (class "Default")
      (node (ref "H10") (pin "2") (pinfunction "2_2") (pintype "input+no_connect"))
    )
    (net (code "80") (name "unconnected-(H12-Pad3)") (class "Default")
      (node (ref "H12") (pin "3") (pinfunction "3_3") (pintype "unspecified"))
    )
    (net (code "81") (name "unconnected-(H12-Pad4)") (class "Default")
      (node (ref "H12") (pin "4") (pinfunction "4_4") (pintype "unspecified"))
    )
    (net (code "82") (name "unconnected-(SW7-Pad4)") (class "Default")
      (node (ref "SW7") (pin "4") (pinfunction "4_4") (pintype "input+no_connect"))
    )
    (net (code "83") (name "unconnected-(SW7-Pad5)") (class "Default")
      (node (ref "SW7") (pin "5") (pinfunction "5_5") (pintype "input+no_connect"))
    )
    (net (code "84") (name "unconnected-(U16-Pad2)") (class "Default")
      (node (ref "U16") (pin "2") (pinfunction "2_2") (pintype "unspecified+no_connect"))
    )
    (net (code "85") (name "unconnected-(U20-NC-Pad4)") (class "Default")
      (node (ref "U20") (pin "4") (pinfunction "NC_4") (pintype "unspecified+no_connect"))
    )
    (net (code "86") (name "unconnected-(U21-Pad1)") (class "Default")
      (node (ref "U21") (pin "1") (pinfunction "1_1") (pintype "input+no_connect"))
    )
    (net (code "87") (name "unconnected-(U22-Pad1)") (class "Default")
      (node (ref "U22") (pin "1") (pinfunction "1_1") (pintype "input+no_connect"))
    )
    (net (code "88") (name "unconnected-(U23-Pad1)") (class "Default")
      (node (ref "U23") (pin "1") (pinfunction "1_1") (pintype "input+no_connect"))
    )
    (net (code "89") (name "unconnected-(U24-Pad1)") (class "Default")
      (node (ref "U24") (pin "1") (pinfunction "1_1") (pintype "input+no_connect"))
    )
    (net (code "90") (name "unconnected-(U28-Pad7)") (class "Default")
      (node (ref "U28") (pin "7") (pinfunction "7_7") (pintype "unspecified"))
    )
    (net (code "91") (name "unconnected-(U28-Pad8)") (class "Default")
      (node (ref "U28") (pin "8") (pinfunction "8_8") (pintype "unspecified"))
    )
  )
)
